# button_configuration.net
KiCad netlist of a schematic drawn in EAGLE
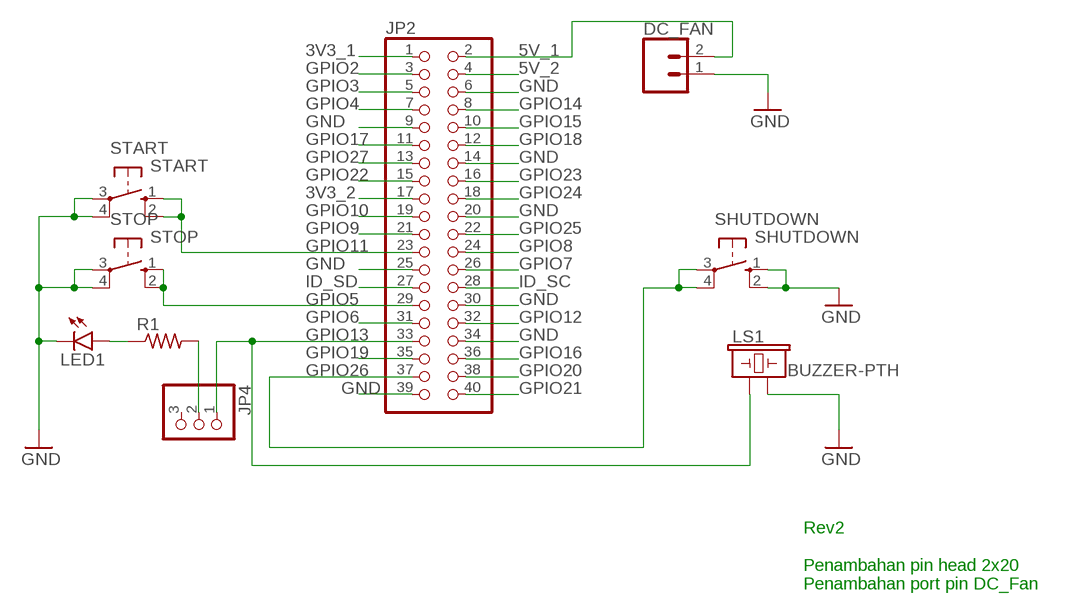
[diagram p0: schematic, sheet 1]

(export (version "E")
  (design (tool "Eeschema 10.0.6"))
  (components
    (comp (ref "DC_FAN")
      (value "CONN_02")
      (footprint "eagle-import:1X02")
      (libsource (lib "eagle-import") (part "CONN_02"))
    )
    (comp (ref "JP2")
      (value "PINHD-2X20-BIG")
      (footprint "eagle-import:2X20-BIG")
      (libsource (lib "eagle-import") (part "PINHD-2X20-BIG"))
    )
    (comp (ref "JP4")
      (value "PINHD-1X3")
      (footprint "eagle-import:1X03")
      (libsource (lib "eagle-import") (part "PINHD-1X3"))
    )
    (comp (ref "LED1")
      (value "LED5MM")
      (footprint "eagle-import:LED5MM")
      (libsource (lib "eagle-import") (part "LED5MM"))
    )
    (comp (ref "LS1")
      (value "BUZZER-PTH")
      (footprint "eagle-import:BUZZER-12MM")
      (libsource (lib "eagle-import") (part "BUZZER-PTH"))
    )
    (comp (ref "R1")
      (value "R-US_0207/10")
      (footprint "eagle-import:0207_10")
      (libsource (lib "eagle-import") (part "R-US_0207/10"))
    )
    (comp (ref "SHUTDOWN")
      (value "SHUTDOWN")
      (footprint "eagle-import:B3F-40XX")
      (fields (field (name "MF") "OMRON COMPONENTS USA") (field (name "MPN") "B3F-4000"))
      (libsource (lib "eagle-import") (part "40-XX"))
    )
    (comp (ref "START")
      (value "START")
      (footprint "eagle-import:B3F-40XX")
      (fields (field (name "MF") "OMRON COMPONENTS USA") (field (name "MPN") "B3F-4000"))
      (libsource (lib "eagle-import") (part "40-XX"))
    )
    (comp (ref "STOP")
      (value "STOP")
      (footprint "eagle-import:B3F-40XX")
      (fields (field (name "MF") "OMRON COMPONENTS USA") (field (name "MPN") "B3F-4000"))
      (libsource (lib "eagle-import") (part "40-XX"))
    )
  )
  (nets
    (net (code "1") (name "/3V3_1") (class "Default")
      (node (ref "JP2") (pin "1") (pinfunction "1_1") (pintype "passive"))
    )
    (net (code "2") (name "/3V3_2") (class "Default")
      (node (ref "JP2") (pin "17") (pinfunction "17_17") (pintype "passive"))
    )
    (net (code "3") (name "/5V_1") (class "Default")
      (node (ref "DC_FAN") (pin "2") (pinfunction "2_2") (pintype "passive"))
      (node (ref "JP2") (pin "2") (pinfunction "2_2") (pintype "passive"))
    )
    (net (code "4") (name "/5V_2") (class "Default")
      (node (ref "JP2") (pin "4") (pinfunction "4_4") (pintype "passive"))
    )
    (net (code "5") (name "/GPIO2") (class "Default")
      (node (ref "JP2") (pin "3") (pinfunction "3_3") (pintype "passive"))
    )
    (net (code "6") (name "/GPIO3") (class "Default")
      (node (ref "JP2") (pin "5") (pinfunction "5_5") (pintype "passive"))
    )
    (net (code "7") (name "/GPIO4") (class "Default")
      (node (ref "JP2") (pin "7") (pinfunction "7_7") (pintype "passive"))
    )
    (net (code "8") (name "/GPIO5") (class "Default")
      (node (ref "JP2") (pin "29") (pinfunction "29_29") (pintype "passive"))
      (node (ref "STOP") (pin "1") (pinfunction "S_1") (pintype "passive"))
      (node (ref "STOP") (pin "2") (pinfunction "S1_2") (pintype "passive"))
    )
    (net (code "9") (name "/GPIO6") (class "Default")
      (node (ref "JP2") (pin "31") (pinfunction "31_31") (pintype "passive"))
    )
    (net (code "10") (name "/GPIO7") (class "Default")
      (node (ref "JP2") (pin "26") (pinfunction "26_26") (pintype "passive"))
    )
    (net (code "11") (name "/GPIO8") (class "Default")
      (node (ref "JP2") (pin "24") (pinfunction "24_24") (pintype "passive"))
    )
    (net (code "12") (name "/GPIO9") (class "Default")
      (node (ref "JP2") (pin "21") (pinfunction "21_21") (pintype "passive"))
    )
    (net (code "13") (name "/GPIO10") (class "Default")
      (node (ref "JP2") (pin "19") (pinfunction "19_19") (pintype "passive"))
    )
    (net (code "14") (name "/GPIO11") (class "Default")
      (node (ref "JP2") (pin "23") (pinfunction "23_23") (pintype "passive"))
      (node (ref "START") (pin "1") (pinfunction "S_1") (pintype "passive"))
      (node (ref "START") (pin "2") (pinfunction "S1_2") (pintype "passive"))
    )
    (net (code "15") (name "/GPIO12") (class "Default")
      (node (ref "JP2") (pin "32") (pinfunction "32_32") (pintype "passive"))
    )
    (net (code "16") (name "/GPIO13") (class "Default")
      (node (ref "JP2") (pin "33") (pinfunction "33_33") (pintype "passive"))
      (node (ref "JP4") (pin "1") (pinfunction "1_1") (pintype "passive"))
      (node (ref "LS1") (pin "+") (pinfunction "1_+") (pintype "passive"))
    )
    (net (code "17") (name "/GPIO14") (class "Default")
      (node (ref "JP2") (pin "8") (pinfunction "8_8") (pintype "passive"))
    )
    (net (code "18") (name "/GPIO15") (class "Default")
      (node (ref "JP2") (pin "10") (pinfunction "10_10") (pintype "passive"))
    )
    (net (code "19") (name "/GPIO16") (class "Default")
      (node (ref "JP2") (pin "36") (pinfunction "36_36") (pintype "passive"))
    )
    (net (code "20") (name "/GPIO17") (class "Default")
      (node (ref "JP2") (pin "11") (pinfunction "11_11") (pintype "passive"))
    )
    (net (code "21") (name "/GPIO18") (class "Default")
      (node (ref "JP2") (pin "12") (pinfunction "12_12") (pintype "passive"))
    )
    (net (code "22") (name "/GPIO19") (class "Default")
      (node (ref "JP2") (pin "35") (pinfunction "35_35") (pintype "passive"))
    )
    (net (code "23") (name "/GPIO20") (class "Default")
      (node (ref "JP2") (pin "38") (pinfunction "38_38") (pintype "passive"))
    )
    (net (code "24") (name "/GPIO21") (class "Default")
      (node (ref "JP2") (pin "40") (pinfunction "40_40") (pintype "passive"))
    )
    (net (code "25") (name "/GPIO22") (class "Default")
      (node (ref "JP2") (pin "15") (pinfunction "15_15") (pintype "passive"))
    )
    (net (code "26") (name "/GPIO23") (class "Default")
      (node (ref "JP2") (pin "16") (pinfunction "16_16") (pintype "passive"))
    )
    (net (code "27") (name "/GPIO24") (class "Default")
      (node (ref "JP2") (pin "18") (pinfunction "18_18") (pintype "passive"))
    )
    (net (code "28") (name "/GPIO25") (class "Default")
      (node (ref "JP2") (pin "22") (pinfunction "22_22") (pintype "passive"))
    )
    (net (code "29") (name "/GPIO26") (class "Default")
      (node (ref "JP2") (pin "37") (pinfunction "37_37") (pintype "passive"))
      (node (ref "SHUTDOWN") (pin "3") (pinfunction "P_3") (pintype "passive"))
      (node (ref "SHUTDOWN") (pin "4") (pinfunction "P1_4") (pintype "passive"))
    )
    (net (code "30") (name "/GPIO27") (class "Default")
      (node (ref "JP2") (pin "13") (pinfunction "13_13") (pintype "passive"))
    )
    (net (code "31") (name "/ID_SC") (class "Default")
      (node (ref "JP2") (pin "28") (pinfunction "28_28") (pintype "passive"))
    )
    (net (code "32") (name "/ID_SD") (class "Default")
      (node (ref "JP2") (pin "27") (pinfunction "27_27") (pintype "passive"))
    )
    (net (code "33") (name "GND") (class "Default")
      (node (ref "DC_FAN") (pin "1") (pinfunction "1_1") (pintype "passive"))
      (node (ref "JP2") (pin "14") (pinfunction "14_14") (pintype "passive"))
      (node (ref "JP2") (pin "20") (pinfunction "20_20") (pintype "passive"))
      (node (ref "JP2") (pin "25") (pinfunction "25_25") (pintype "passive"))
      (node (ref "JP2") (pin "30") (pinfunction "30_30") (pintype "passive"))
      (node (ref "JP2") (pin "34") (pinfunction "34_34") (pintype "passive"))
      (node (ref "JP2") (pin "39") (pinfunction "39_39") (pintype "passive"))
      (node (ref "JP2") (pin "6") (pinfunction "6_6") (pintype "passive"))
      (node (ref "JP2") (pin "9") (pinfunction "9_9") (pintype "passive"))
      (node (ref "LED1") (pin "K") (pinfunction "C_K") (pintype "passive"))
      (node (ref "LS1") (pin "-") (pinfunction "2_-") (pintype "passive"))
      (node (ref "SHUTDOWN") (pin "1") (pinfunction "S_1") (pintype "passive"))
      (node (ref "SHUTDOWN") (pin "2") (pinfunction "S1_2") (pintype "passive"))
      (node (ref "START") (pin "3") (pinfunction "P_3") (pintype "passive"))
      (node (ref "START") (pin "4") (pinfunction "P1_4") (pintype "passive"))
      (node (ref "STOP") (pin "3") (pinfunction "P_3") (pintype "passive"))
      (node (ref "STOP") (pin "4") (pinfunction "P1_4") (pintype "passive"))
    )
    (net (code "34") (name "Net-(JP4-Pad2)") (class "Default")
      (node (ref "JP4") (pin "2") (pinfunction "2_2") (pintype "passive"))
      (node (ref "R1") (pin "2") (pinfunction "2_2") (pintype "passive"))
    )
    (net (code "35") (name "Net-(LED1-PadA)") (class "Default")
      (node (ref "LED1") (pin "A") (pinfunction "A_A") (pintype "passive"))
      (node (ref "R1") (pin "1") (pinfunction "1_1") (pintype "passive"))
    )
    (net (code "36") (name "unconnected-(JP4-Pad3)") (class "Default")
      (node (ref "JP4") (pin "3") (pinfunction "3_3") (pintype "passive"))
    )
  )
)
